# Board_settlemen.net
KiCad netlist of a schematic drawn in EAGLE
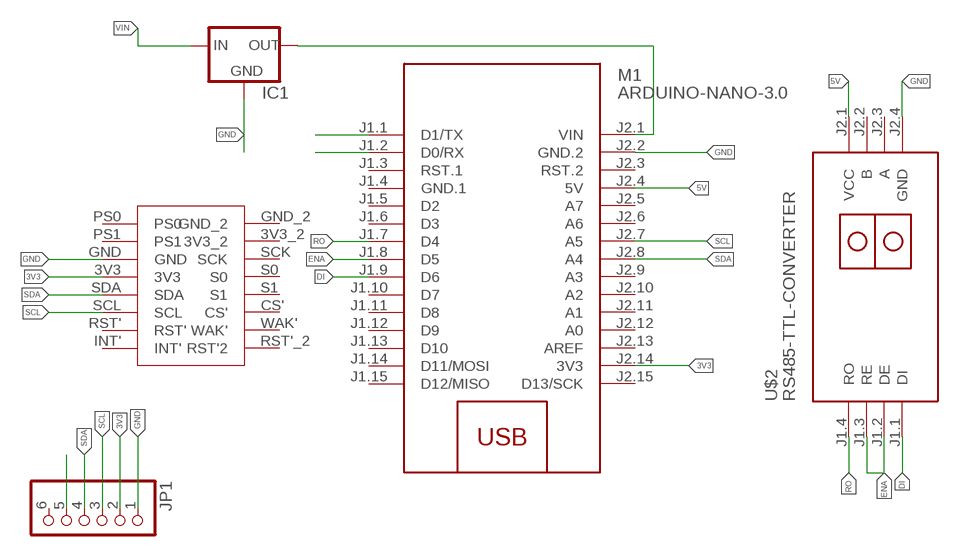
[diagram p0: schematic, sheet 1]

(export (version "E")
  (design (tool "Eeschema 10.0.6"))
  (components
    (comp (ref "IC1")
      (value "78MXXS")
      (footprint "eagle-import:78MXXS")
      (libsource (lib "eagle-import") (part "78MXXS"))
    )
    (comp (ref "JP1")
      (value "PINHD-1X6")
      (footprint "eagle-import:1X06")
      (libsource (lib "eagle-import") (part "PINHD-1X6"))
    )
    (comp (ref "M1")
      (value "ARDUINO-NANO-3.0")
      (footprint "eagle-import:ARDUINO-NANO-3.0")
      (libsource (lib "eagle-import") (part "ARDUINO-NANO-3.0"))
    )
    (comp (ref "U$1")
      (value "BNO080")
      (footprint "eagle-import:BNO080")
      (libsource (lib "eagle-import") (part "BNO080"))
    )
    (comp (ref "U$2")
      (value "RS485-TTL-CONVERTER")
      (footprint "eagle-import:RS485-TTL-CONVERTER")
      (libsource (lib "eagle-import") (part "RS485-TTL-CONVERTER"))
    )
  )
  (nets
    (net (code "1") (name "/GND.1") (class "Default")
      (node (ref "M1") (pin "J1.4") (pinfunction "GND.1_J1.4") (pintype "power_in"))
    )
    (net (code "2") (name "3V3") (class "Default")
      (node (ref "JP1") (pin "2") (pinfunction "2_2") (pintype "passive"))
      (node (ref "M1") (pin "J2.14") (pinfunction "3V3_J2.14") (pintype "power_in"))
      (node (ref "U$1") (pin "3V3") (pinfunction "3V3_3V3") (pintype "bidirectional"))
    )
    (net (code "3") (name "5V") (class "Default")
      (node (ref "M1") (pin "J2.4") (pinfunction "5V_J2.4") (pintype "power_in"))
      (node (ref "U$2") (pin "J2.1") (pinfunction "VCC_J2.1") (pintype "power_in"))
    )
    (net (code "4") (name "DI") (class "Default")
      (node (ref "M1") (pin "J1.9") (pinfunction "D6_J1.9") (pintype "bidirectional"))
      (node (ref "U$2") (pin "J1.1") (pinfunction "DI_J1.1") (pintype "passive"))
    )
    (net (code "5") (name "ENA") (class "Default")
      (node (ref "M1") (pin "J1.8") (pinfunction "D5_J1.8") (pintype "bidirectional"))
      (node (ref "U$2") (pin "J1.2") (pinfunction "DE_J1.2") (pintype "passive"))
      (node (ref "U$2") (pin "J1.3") (pinfunction "RE_J1.3") (pintype "passive"))
    )
    (net (code "6") (name "GND") (class "Default")
      (node (ref "IC1") (pin "GND") (pinfunction "GND_GND") (pintype "input"))
      (node (ref "JP1") (pin "1") (pinfunction "1_1") (pintype "passive"))
      (node (ref "M1") (pin "J2.2") (pinfunction "GND.2_J2.2") (pintype "power_in"))
      (node (ref "U$1") (pin "GND") (pinfunction "GND_GND") (pintype "bidirectional"))
      (node (ref "U$2") (pin "J2.4") (pinfunction "GND_J2.4") (pintype "power_in"))
    )
    (net (code "7") (name "Net-(M1-VIN)") (class "Default")
      (node (ref "IC1") (pin "OUT") (pinfunction "OUT_OUT") (pintype "passive"))
      (node (ref "M1") (pin "J2.1") (pinfunction "VIN_J2.1") (pintype "power_in"))
    )
    (net (code "8") (name "RO") (class "Default")
      (node (ref "M1") (pin "J1.7") (pinfunction "D4_J1.7") (pintype "bidirectional"))
      (node (ref "U$2") (pin "J1.4") (pinfunction "RO_J1.4") (pintype "passive"))
    )
    (net (code "9") (name "SCL") (class "Default")
      (node (ref "JP1") (pin "3") (pinfunction "3_3") (pintype "passive"))
      (node (ref "M1") (pin "J2.7") (pinfunction "A5_J2.7") (pintype "bidirectional"))
      (node (ref "U$1") (pin "SCL") (pinfunction "SCL_SCL") (pintype "bidirectional"))
    )
    (net (code "10") (name "SDA") (class "Default")
      (node (ref "JP1") (pin "4") (pinfunction "4_4") (pintype "passive"))
      (node (ref "M1") (pin "J2.8") (pinfunction "A4_J2.8") (pintype "bidirectional"))
      (node (ref "U$1") (pin "SDA") (pinfunction "SDA_SDA") (pintype "bidirectional"))
    )
    (net (code "11") (name "VIN") (class "Default")
      (node (ref "IC1") (pin "IN") (pinfunction "IN_IN") (pintype "input"))
    )
    (net (code "12") (name "unconnected-(JP1-Pad5)") (class "Default")
      (node (ref "JP1") (pin "5") (pinfunction "5_5") (pintype "passive"))
    )
    (net (code "13") (name "unconnected-(JP1-Pad6)") (class "Default")
      (node (ref "JP1") (pin "6") (pinfunction "6_6") (pintype "passive"))
    )
    (net (code "14") (name "unconnected-(M1-A0-PadJ2.12)") (class "Default")
      (node (ref "M1") (pin "J2.12") (pinfunction "A0_J2.12") (pintype "bidirectional"))
    )
    (net (code "15") (name "unconnected-(M1-A1-PadJ2.11)") (class "Default")
      (node (ref "M1") (pin "J2.11") (pinfunction "A1_J2.11") (pintype "bidirectional"))
    )
    (net (code "16") (name "unconnected-(M1-A2-PadJ2.10)") (class "Default")
      (node (ref "M1") (pin "J2.10") (pinfunction "A2_J2.10") (pintype "bidirectional"))
    )
    (net (code "17") (name "unconnected-(M1-A3-PadJ2.9)") (class "Default")
      (node (ref "M1") (pin "J2.9") (pinfunction "A3_J2.9") (pintype "bidirectional"))
    )
    (net (code "18") (name "unconnected-(M1-A6-PadJ2.6)") (class "Default")
      (node (ref "M1") (pin "J2.6") (pinfunction "A6_J2.6") (pintype "bidirectional"))
    )
    (net (code "19") (name "unconnected-(M1-A7-PadJ2.5)") (class "Default")
      (node (ref "M1") (pin "J2.5") (pinfunction "A7_J2.5") (pintype "bidirectional"))
    )
    (net (code "20") (name "unconnected-(M1-AREF-PadJ2.13)") (class "Default")
      (node (ref "M1") (pin "J2.13") (pinfunction "AREF_J2.13") (pintype "bidirectional"))
    )
    (net (code "21") (name "unconnected-(M1-D0{slash}RX-PadJ1.2)") (class "Default")
      (node (ref "M1") (pin "J1.2") (pinfunction "D0/RX_J1.2") (pintype "bidirectional"))
    )
    (net (code "22") (name "unconnected-(M1-D1{slash}TX-PadJ1.1)") (class "Default")
      (node (ref "M1") (pin "J1.1") (pinfunction "D1/TX_J1.1") (pintype "bidirectional"))
    )
    (net (code "23") (name "unconnected-(M1-D2-PadJ1.5)") (class "Default")
      (node (ref "M1") (pin "J1.5") (pinfunction "D2_J1.5") (pintype "bidirectional"))
    )
    (net (code "24") (name "unconnected-(M1-D3-PadJ1.6)") (class "Default")
      (node (ref "M1") (pin "J1.6") (pinfunction "D3_J1.6") (pintype "bidirectional"))
    )
    (net (code "25") (name "unconnected-(M1-D7-PadJ1.10)") (class "Default")
      (node (ref "M1") (pin "J1.10") (pinfunction "D7_J1.10") (pintype "bidirectional"))
    )
    (net (code "26") (name "unconnected-(M1-D8-PadJ1.11)") (class "Default")
      (node (ref "M1") (pin "J1.11") (pinfunction "D8_J1.11") (pintype "bidirectional"))
    )
    (net (code "27") (name "unconnected-(M1-D9-PadJ1.12)") (class "Default")
      (node (ref "M1") (pin "J1.12") (pinfunction "D9_J1.12") (pintype "bidirectional"))
    )
    (net (code "28") (name "unconnected-(M1-D10-PadJ1.13)") (class "Default")
      (node (ref "M1") (pin "J1.13") (pinfunction "D10_J1.13") (pintype "bidirectional"))
    )
    (net (code "29") (name "unconnected-(M1-D11{slash}MOSI-PadJ1.14)") (class "Default")
      (node (ref "M1") (pin "J1.14") (pinfunction "D11/MOSI_J1.14") (pintype "bidirectional"))
    )
    (net (code "30") (name "unconnected-(M1-D12{slash}MISO-PadJ1.15)") (class "Default")
      (node (ref "M1") (pin "J1.15") (pinfunction "D12/MISO_J1.15") (pintype "bidirectional"))
    )
    (net (code "31") (name "unconnected-(M1-D13{slash}SCK-PadJ2.15)") (class "Default")
      (node (ref "M1") (pin "J2.15") (pinfunction "D13/SCK_J2.15") (pintype "bidirectional"))
    )
    (net (code "32") (name "unconnected-(M1-RST.1-PadJ1.3)") (class "Default")
      (node (ref "M1") (pin "J1.3") (pinfunction "RST.1_J1.3") (pintype "bidirectional"))
    )
    (net (code "33") (name "unconnected-(M1-RST.2-PadJ2.3)") (class "Default")
      (node (ref "M1") (pin "J2.3") (pinfunction "RST.2_J2.3") (pintype "bidirectional"))
    )
    (net (code "34") (name "unconnected-(U$1-Pad3V3_2)") (class "Default")
      (node (ref "U$1") (pin "3V3_2") (pinfunction "3V3_2_3V3_2") (pintype "bidirectional"))
    )
    (net (code "35") (name "unconnected-(U$1-PadCS')") (class "Default")
      (node (ref "U$1") (pin "CS'") (pinfunction "CS'_CS'") (pintype "bidirectional"))
    )
    (net (code "36") (name "unconnected-(U$1-PadGND_2)") (class "Default")
      (node (ref "U$1") (pin "GND_2") (pinfunction "GND_2_GND_2") (pintype "bidirectional"))
    )
    (net (code "37") (name "unconnected-(U$1-PadINT')") (class "Default")
      (node (ref "U$1") (pin "INT'") (pinfunction "INT'_INT'") (pintype "bidirectional"))
    )
    (net (code "38") (name "unconnected-(U$1-PadPS0)") (class "Default")
      (node (ref "U$1") (pin "PS0") (pinfunction "PS0_PS0") (pintype "bidirectional"))
    )
    (net (code "39") (name "unconnected-(U$1-PadPS1)") (class "Default")
      (node (ref "U$1") (pin "PS1") (pinfunction "PS1_PS1") (pintype "bidirectional"))
    )
    (net (code "40") (name "unconnected-(U$1-PadRST')") (class "Default")
      (node (ref "U$1") (pin "RST'") (pinfunction "RST'_RST'") (pintype "bidirectional"))
    )
    (net (code "41") (name "unconnected-(U$1-PadS0)") (class "Default")
      (node (ref "U$1") (pin "S0") (pinfunction "S0_S0") (pintype "bidirectional"))
    )
    (net (code "42") (name "unconnected-(U$1-PadS1)") (class "Default")
      (node (ref "U$1") (pin "S1") (pinfunction "S1_S1") (pintype "bidirectional"))
    )
    (net (code "43") (name "unconnected-(U$1-PadSCK)") (class "Default")
      (node (ref "U$1") (pin "SCK") (pinfunction "SCK_SCK") (pintype "bidirectional"))
    )
    (net (code "44") (name "unconnected-(U$1-PadWAK')") (class "Default")
      (node (ref "U$1") (pin "WAK'") (pinfunction "WAK'_WAK'") (pintype "bidirectional"))
    )
    (net (code "45") (name "unconnected-(U$1-RST'2-PadRST'_2)") (class "Default")
      (node (ref "U$1") (pin "RST'_2") (pinfunction "RST'2_RST'_2") (pintype "bidirectional"))
    )
    (net (code "46") (name "unconnected-(U$2-A-PadJ2.3)") (class "Default")
      (node (ref "U$2") (pin "J2.3") (pinfunction "A_J2.3") (pintype "passive"))
    )
    (net (code "47") (name "unconnected-(U$2-B-PadJ2.2)") (class "Default")
      (node (ref "U$2") (pin "J2.2") (pinfunction "B_J2.2") (pintype "passive"))
    )
  )
)
